# T41_TPad.net
KiCad netlist of a schematic drawn in EAGLE
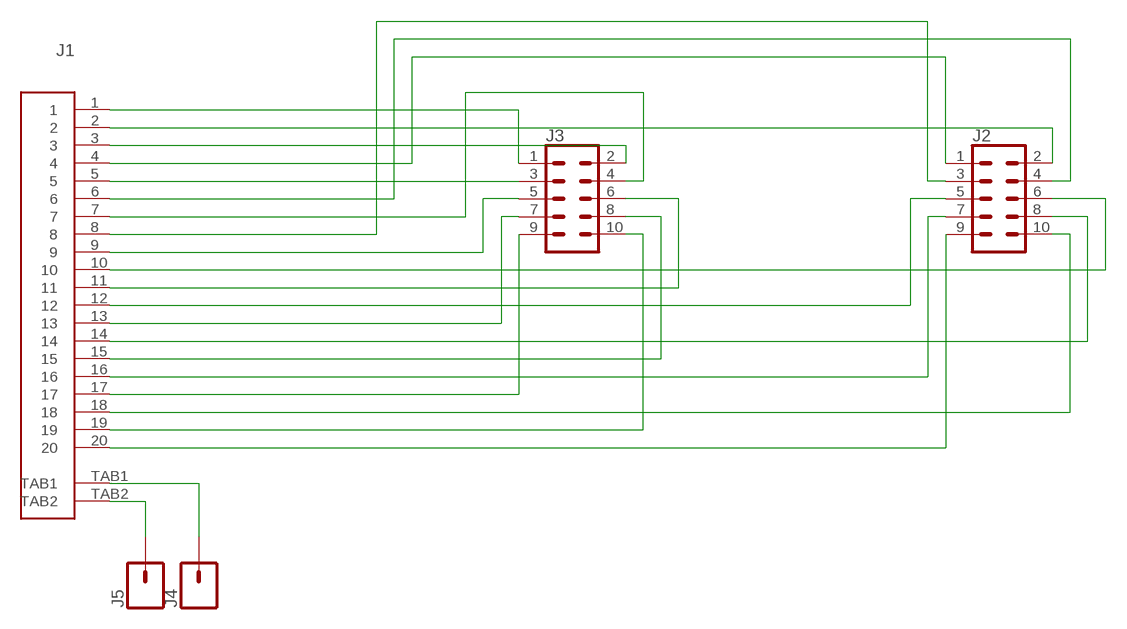
[diagram p0: schematic, sheet 1]

(export (version "E")
  (design (tool "Eeschema 10.0.6"))
  (components
    (comp (ref "J1")
      (value "DF12-20DP")
      (footprint "eagle-import:DF12-20DP")
      (libsource (lib "eagle-import") (part "DF12-20DP"))
    )
    (comp (ref "J2")
      (value "CONN_05X2NO_SILK")
      (footprint "eagle-import:2X5_NOSILK")
      (libsource (lib "eagle-import") (part "CONN_05X2NO_SILK"))
    )
    (comp (ref "J3")
      (value "CONN_05X2NO_SILK")
      (footprint "eagle-import:2X5_NOSILK")
      (libsource (lib "eagle-import") (part "CONN_05X2NO_SILK"))
    )
    (comp (ref "J4")
      (value "CONN_01")
      (footprint "eagle-import:1X01")
      (libsource (lib "eagle-import") (part "CONN_01"))
    )
    (comp (ref "J5")
      (value "CONN_01")
      (footprint "eagle-import:1X01")
      (libsource (lib "eagle-import") (part "CONN_01"))
    )
  )
  (nets
    (net (code "1") (name "Net-(J1-Pad1)") (class "Default")
      (node (ref "J1") (pin "1") (pinfunction "1_1") (pintype "bidirectional"))
      (node (ref "J3") (pin "1") (pinfunction "1_1") (pintype "passive"))
    )
    (net (code "2") (name "Net-(J1-Pad2)") (class "Default")
      (node (ref "J1") (pin "2") (pinfunction "2_2") (pintype "bidirectional"))
      (node (ref "J2") (pin "2") (pinfunction "2_2") (pintype "passive"))
    )
    (net (code "3") (name "Net-(J1-Pad3)") (class "Default")
      (node (ref "J1") (pin "3") (pinfunction "3_3") (pintype "bidirectional"))
      (node (ref "J3") (pin "2") (pinfunction "2_2") (pintype "passive"))
    )
    (net (code "4") (name "Net-(J1-Pad4)") (class "Default")
      (node (ref "J1") (pin "4") (pinfunction "4_4") (pintype "bidirectional"))
      (node (ref "J2") (pin "1") (pinfunction "1_1") (pintype "passive"))
    )
    (net (code "5") (name "Net-(J1-Pad5)") (class "Default")
      (node (ref "J1") (pin "5") (pinfunction "5_5") (pintype "bidirectional"))
      (node (ref "J3") (pin "3") (pinfunction "3_3") (pintype "passive"))
    )
    (net (code "6") (name "Net-(J1-Pad6)") (class "Default")
      (node (ref "J1") (pin "6") (pinfunction "6_6") (pintype "bidirectional"))
      (node (ref "J2") (pin "4") (pinfunction "4_4") (pintype "passive"))
    )
    (net (code "7") (name "Net-(J1-Pad7)") (class "Default")
      (node (ref "J1") (pin "7") (pinfunction "7_7") (pintype "bidirectional"))
      (node (ref "J3") (pin "4") (pinfunction "4_4") (pintype "passive"))
    )
    (net (code "8") (name "Net-(J1-Pad8)") (class "Default")
      (node (ref "J1") (pin "8") (pinfunction "8_8") (pintype "bidirectional"))
      (node (ref "J2") (pin "3") (pinfunction "3_3") (pintype "passive"))
    )
    (net (code "9") (name "Net-(J1-Pad9)") (class "Default")
      (node (ref "J1") (pin "9") (pinfunction "9_9") (pintype "bidirectional"))
      (node (ref "J3") (pin "5") (pinfunction "5_5") (pintype "passive"))
    )
    (net (code "10") (name "Net-(J1-Pad10)") (class "Default")
      (node (ref "J1") (pin "10") (pinfunction "10_10") (pintype "bidirectional"))
      (node (ref "J2") (pin "6") (pinfunction "6_6") (pintype "passive"))
    )
    (net (code "11") (name "Net-(J1-Pad11)") (class "Default")
      (node (ref "J1") (pin "11") (pinfunction "11_11") (pintype "bidirectional"))
      (node (ref "J3") (pin "6") (pinfunction "6_6") (pintype "passive"))
    )
    (net (code "12") (name "Net-(J1-Pad12)") (class "Default")
      (node (ref "J1") (pin "12") (pinfunction "12_12") (pintype "bidirectional"))
      (node (ref "J2") (pin "5") (pinfunction "5_5") (pintype "passive"))
    )
    (net (code "13") (name "Net-(J1-Pad13)") (class "Default")
      (node (ref "J1") (pin "13") (pinfunction "13_13") (pintype "bidirectional"))
      (node (ref "J3") (pin "7") (pinfunction "7_7") (pintype "passive"))
    )
    (net (code "14") (name "Net-(J1-Pad14)") (class "Default")
      (node (ref "J1") (pin "14") (pinfunction "14_14") (pintype "bidirectional"))
      (node (ref "J2") (pin "8") (pinfunction "8_8") (pintype "passive"))
    )
    (net (code "15") (name "Net-(J1-Pad15)") (class "Default")
      (node (ref "J1") (pin "15") (pinfunction "15_15") (pintype "bidirectional"))
      (node (ref "J3") (pin "8") (pinfunction "8_8") (pintype "passive"))
    )
    (net (code "16") (name "Net-(J1-Pad16)") (class "Default")
      (node (ref "J1") (pin "16") (pinfunction "16_16") (pintype "bidirectional"))
      (node (ref "J2") (pin "7") (pinfunction "7_7") (pintype "passive"))
    )
    (net (code "17") (name "Net-(J1-Pad17)") (class "Default")
      (node (ref "J1") (pin "17") (pinfunction "17_17") (pintype "bidirectional"))
      (node (ref "J3") (pin "9") (pinfunction "9_9") (pintype "passive"))
    )
    (net (code "18") (name "Net-(J1-Pad18)") (class "Default")
      (node (ref "J1") (pin "18") (pinfunction "18_18") (pintype "bidirectional"))
      (node (ref "J2") (pin "10") (pinfunction "10_10") (pintype "passive"))
    )
    (net (code "19") (name "Net-(J1-Pad19)") (class "Default")
      (node (ref "J1") (pin "19") (pinfunction "19_19") (pintype "bidirectional"))
      (node (ref "J3") (pin "10") (pinfunction "10_10") (pintype "passive"))
    )
    (net (code "20") (name "Net-(J1-Pad20)") (class "Default")
      (node (ref "J1") (pin "20") (pinfunction "20_20") (pintype "bidirectional"))
      (node (ref "J2") (pin "9") (pinfunction "9_9") (pintype "passive"))
    )
    (net (code "21") (name "Net-(J1-PadTAB1)") (class "Default")
      (node (ref "J1") (pin "TAB1") (pinfunction "TAB1_TAB1") (pintype "bidirectional"))
      (node (ref "J4") (pin "1") (pinfunction "1_1") (pintype "passive"))
    )
    (net (code "22") (name "Net-(J1-PadTAB2)") (class "Default")
      (node (ref "J1") (pin "TAB2") (pinfunction "TAB2_TAB2") (pintype "bidirectional"))
      (node (ref "J5") (pin "1") (pinfunction "1_1") (pintype "passive"))
    )
  )
)
